# STM32.net
KiCad netlist of a schematic drawn in Altium Designer
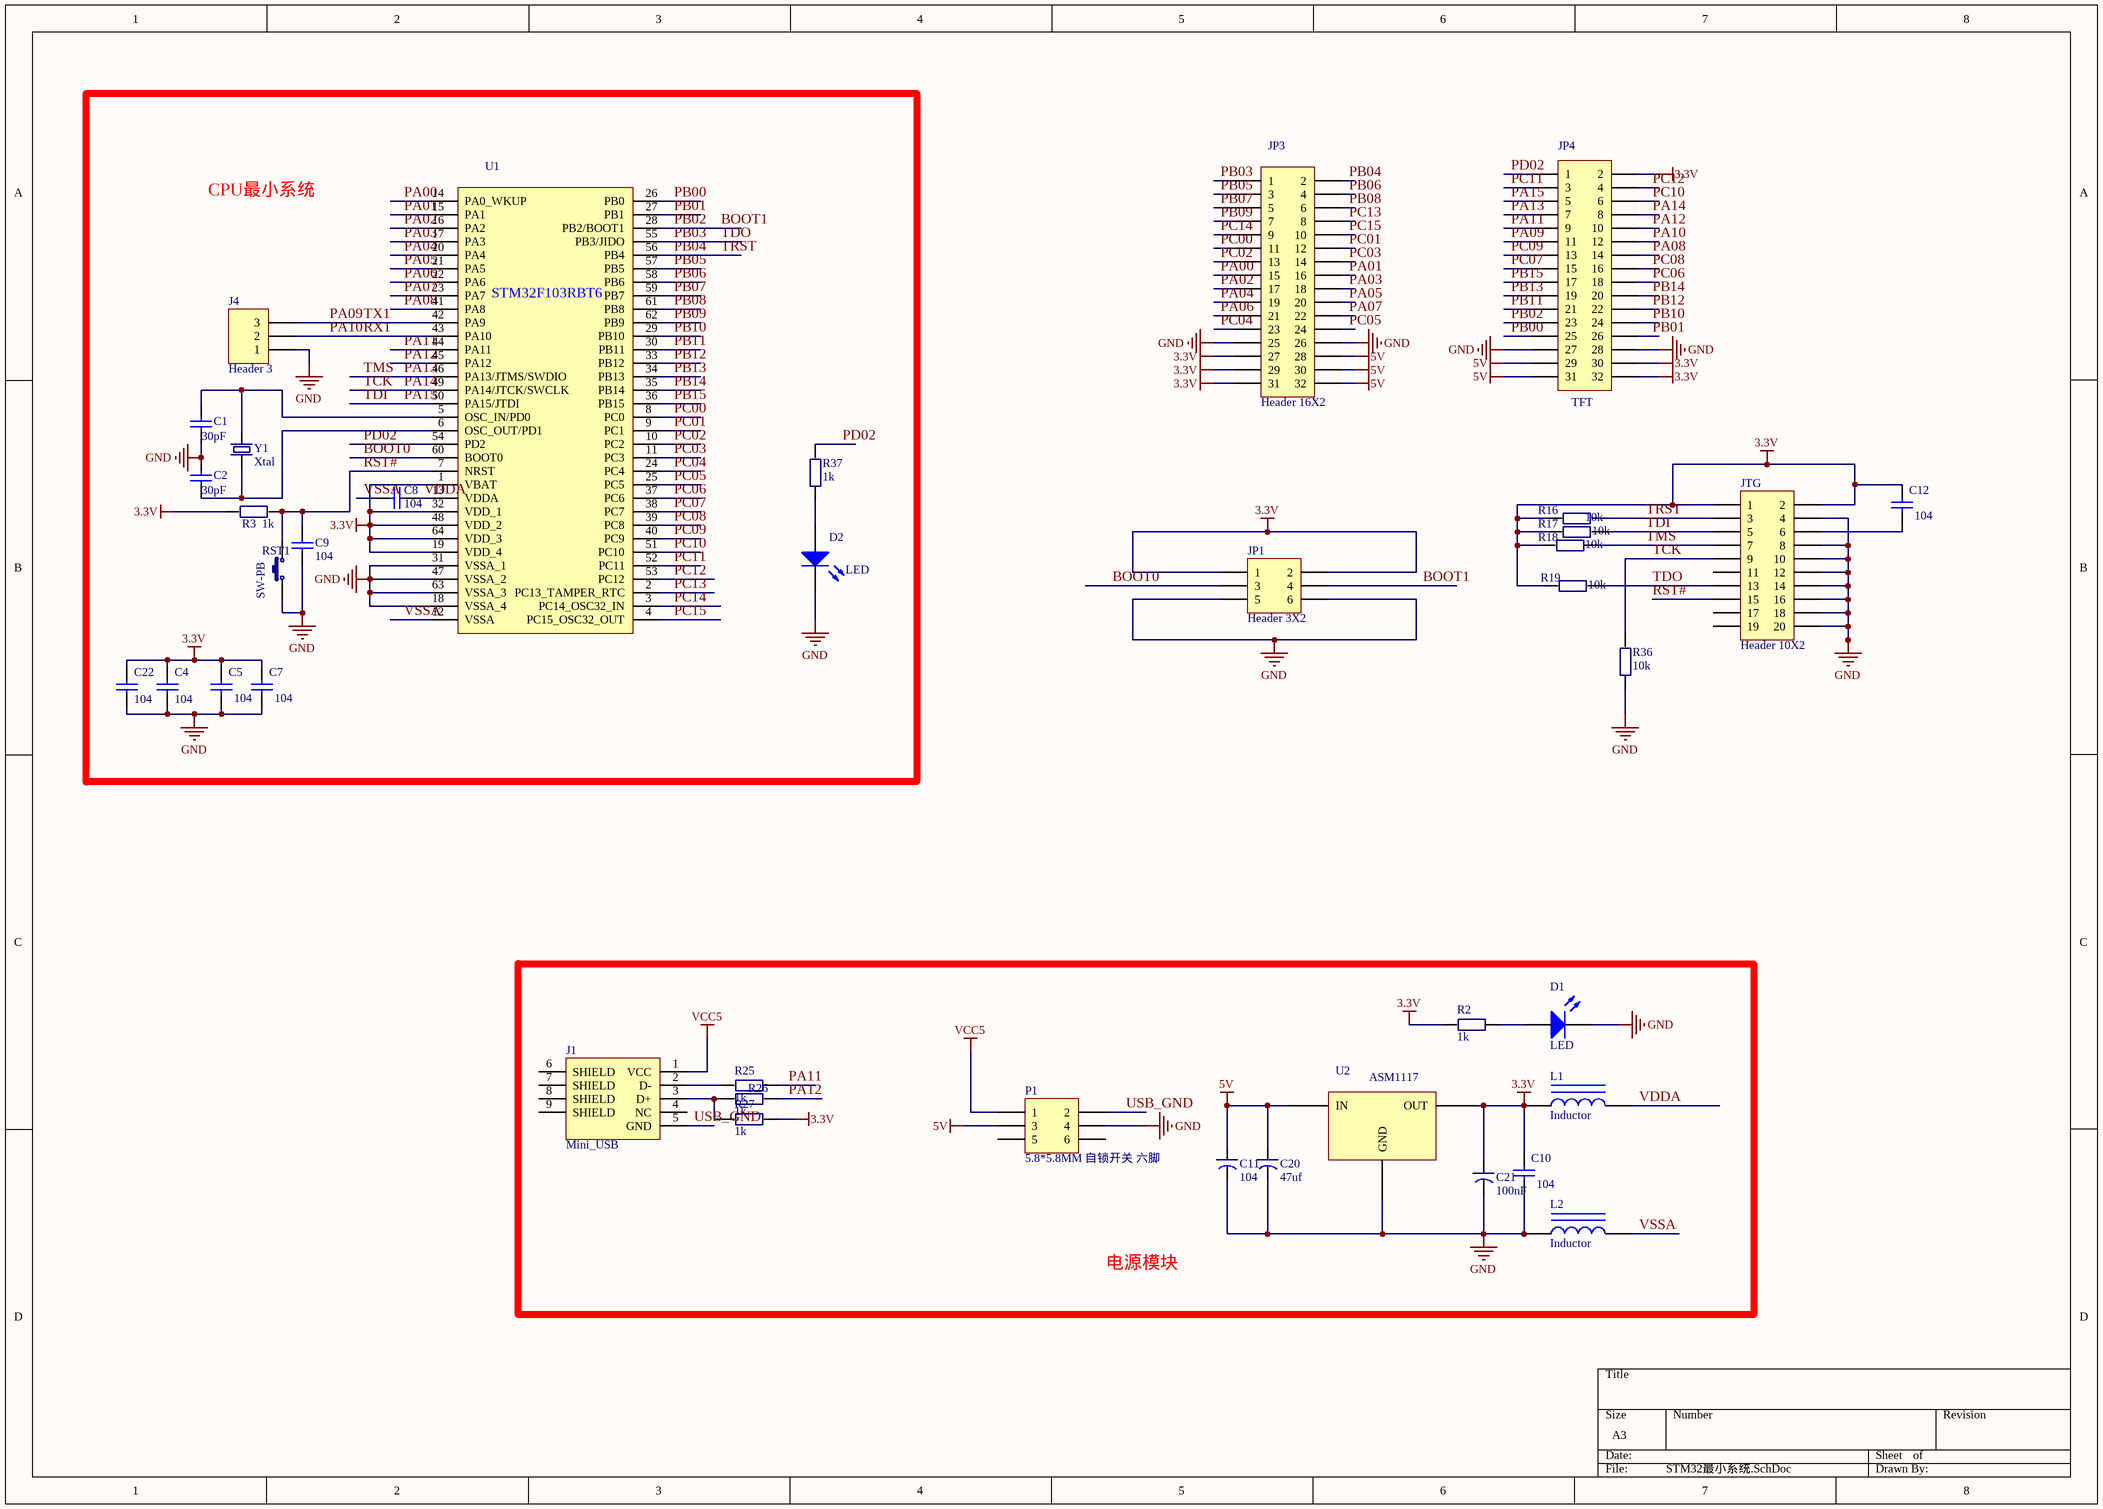
[diagram p0: STM32最小系统.SchDoc]

(export (version "E")
  (design (tool "Eeschema 10.0.6"))
  (components
    (comp (ref "C1")
      (value "30pF")
      (footprint "C0805")
      (description "Capacitor")
      (fields (field (name "Comment") "Cap") (field (name "PUBLISHER") "Altium Limited"))
      (libsource (lib "M051电子称") (part "Cap"))
    )
    (comp (ref "C2")
      (value "30pF")
      (footprint "C0805")
      (description "Capacitor")
      (fields (field (name "Comment") "Cap") (field (name "PUBLISHER") "Altium Limited"))
      (libsource (lib "M051电子称") (part "Cap"))
    )
    (comp (ref "C4")
      (value "104")
      (footprint "C0805")
      (description "Capacitor")
      (fields (field (name "Comment") "Cap") (field (name "PUBLISHER") "Altium Limited"))
      (libsource (lib "M051电子称") (part "Cap"))
    )
    (comp (ref "C5")
      (value "104")
      (footprint "C0805")
      (description "Capacitor")
      (fields (field (name "Comment") "Cap") (field (name "PUBLISHER") "Altium Limited"))
      (libsource (lib "M051电子称") (part "Cap"))
    )
    (comp (ref "C7")
      (value "104")
      (footprint "C0805")
      (description "Capacitor")
      (fields (field (name "Comment") "Cap") (field (name "PUBLISHER") "Altium Limited"))
      (libsource (lib "M051电子称") (part "Cap"))
    )
    (comp (ref "C8")
      (value "104")
      (footprint "C0805")
      (description "Capacitor")
      (fields (field (name "Comment") "Cap") (field (name "PUBLISHER") "Altium Limited"))
      (libsource (lib "M051电子称") (part "Cap"))
    )
    (comp (ref "C9")
      (value "104")
      (footprint "C0805")
      (description "Capacitor")
      (fields (field (name "Comment") "Cap") (field (name "PUBLISHER") "Altium Limited"))
      (libsource (lib "M051电子称") (part "Cap"))
    )
    (comp (ref "C10")
      (value "104")
      (footprint "C0805")
      (description "Capacitor")
      (fields (field (name "Comment") "Cap") (field (name "PUBLISHER") "Altium Limited"))
      (libsource (lib "M051电子称") (part "Cap"))
    )
    (comp (ref "C11")
      (value "104")
      (footprint "C0805")
      (fields (field (name "Comment") "Capacitor"))
      (libsource (lib "My Devices") (part "Capacitor"))
    )
    (comp (ref "C12")
      (value "104")
      (footprint "C0805")
      (description "Capacitor")
      (fields (field (name "Comment") "Cap") (field (name "PUBLISHER") "Altium Limited"))
      (libsource (lib "M051电子称") (part "Cap"))
    )
    (comp (ref "C20")
      (value "47uf")
      (footprint "47uF_25V")
      (fields (field (name "Comment") "Capacitor"))
      (libsource (lib "My Devices") (part "Capacitor"))
    )
    (comp (ref "C21")
      (value "100nF")
      (footprint "47uF_25V")
      (fields (field (name "Comment") "Capacitor"))
      (libsource (lib "My Devices") (part "Capacitor"))
    )
    (comp (ref "C22")
      (value "104")
      (footprint "C0805")
      (description "Capacitor")
      (fields (field (name "Comment") "Cap") (field (name "PUBLISHER") "Altium Limited"))
      (libsource (lib "M051电子称") (part "Cap"))
    )
    (comp (ref "D1") (value "LED") (footprint "0805D") (libsource (lib "My Devices") (part "LED")))
    (comp (ref "D2") (value "LED") (footprint "0805D") (libsource (lib "My Devices") (part "LED")))
    (comp (ref "J1")
      (value "Mini_USB")
      (footprint "Mini_USB")
      (libsource (lib "My Devices") (part "Mini_USB"))
    )
    (comp (ref "J4")
      (value "Header 3")
      (footprint "HDR1X3")
      (description "Header, 3-Pin")
      (fields (field (name "PUBLISHER") "Altium Limited"))
      (libsource (lib "Header Devices") (part "Header 3"))
    )
    (comp (ref "JP1")
      (value "Header 3X2")
      (footprint "HDR2X3")
      (description "Header, 3-Pin, Dual row")
      (fields (field (name "PUBLISHER") "Altium Limited"))
      (libsource (lib "Header Devices") (part "Header 3X2"))
    )
    (comp (ref "JP3")
      (value "Header 16X2")
      (footprint "HDR2X16")
      (description "Header, 16-Pin, Dual row")
      (fields (field (name "PUBLISHER") "Altium Limited"))
      (libsource (lib "Header Devices") (part "Header 16X2"))
    )
    (comp (ref "JP4")
      (value "TFT")
      (footprint "HDR2X16")
      (description "Header, 16-Pin, Dual row")
      (fields (field (name "PUBLISHER") "Altium Limited"))
      (libsource (lib "Header Devices") (part "Header 16X2"))
    )
    (comp (ref "JTG")
      (value "Header 10X2")
      (footprint "HDR2X10")
      (description "Header, 10-Pin, Dual row")
      (fields (field (name "PUBLISHER") "Altium Limited"))
      (libsource (lib "Header Devices") (part "Header 10X2"))
    )
    (comp (ref "L1") (value "Inductor") (footprint "C0805") (libsource (lib "My Devices") (part "Inductor")))
    (comp (ref "L2") (value "Inductor") (footprint "C0805") (libsource (lib "My Devices") (part "Inductor")))
    (comp (ref "P1")
      (value "5.8*5.8MM 自锁开关 六脚")
      (footprint "5.8*5.8MM 自锁开关 六脚")
      (libsource (lib "自制库-程文") (part "5.8*5.8MM 自锁开关 六脚"))
    )
    (comp (ref "R2")
      (value "1k")
      (footprint "R0805")
      (fields (field (name "Comment") "Resistor"))
      (libsource (lib "My Devices") (part "Resistor"))
    )
    (comp (ref "R3")
      (value "1k")
      (footprint "R0805")
      (fields (field (name "Comment") "Resistor"))
      (libsource (lib "My Devices") (part "Resistor"))
    )
    (comp (ref "R16")
      (value "10k")
      (footprint "R0805")
      (fields (field (name "Comment") "Resistor"))
      (libsource (lib "My Devices") (part "Resistor"))
    )
    (comp (ref "R17")
      (value "10k")
      (footprint "R0805")
      (fields (field (name "Comment") "Resistor"))
      (libsource (lib "My Devices") (part "Resistor"))
    )
    (comp (ref "R18")
      (value "10k")
      (footprint "R0805")
      (fields (field (name "Comment") "Resistor"))
      (libsource (lib "My Devices") (part "Resistor"))
    )
    (comp (ref "R19")
      (value "10k")
      (footprint "R0805")
      (fields (field (name "Comment") "Resistor"))
      (libsource (lib "My Devices") (part "Resistor"))
    )
    (comp (ref "R25")
      (value "1k")
      (footprint "R0805")
      (fields (field (name "Comment") "Resistor"))
      (libsource (lib "My Devices") (part "Resistor"))
    )
    (comp (ref "R26")
      (value "1k")
      (footprint "R0805")
      (fields (field (name "Comment") "Resistor"))
      (libsource (lib "My Devices") (part "Resistor"))
    )
    (comp (ref "R27")
      (value "1k")
      (footprint "R0805")
      (fields (field (name "Comment") "Resistor"))
      (libsource (lib "My Devices") (part "Resistor"))
    )
    (comp (ref "R36")
      (value "10k")
      (footprint "R0805")
      (fields (field (name "Comment") "Resistor"))
      (libsource (lib "My Devices") (part "Resistor"))
    )
    (comp (ref "R37")
      (value "1k")
      (footprint "R0805")
      (fields (field (name "Comment") "Resistor"))
      (libsource (lib "My Devices") (part "Resistor"))
    )
    (comp (ref "RST1") (value "SW-PB") (footprint "TD-19XA") (libsource (lib "My Devices") (part "Switch")))
    (comp (ref "U1")
      (value "STM32F103RBT6")
      (footprint "LQFP-64N")
      (libsource (lib "My Devices") (part "STM32F103RBT6"))
    )
    (comp (ref "U2") (value "ASM1117") (footprint "SOT-223") (libsource (lib "电源类集成库") (part "ASM1117")))
    (comp (ref "Y1") (value "Xtal") (footprint "CRYSTAL") (libsource (lib "My Devices") (part "Xtal")))
  )
  (nets
    (net (code "1") (name "/BOOT0") (class "Default")
      (node (ref "JP1") (pin "3") (pinfunction "3_3") (pintype "passive"))
      (node (ref "U1") (pin "60") (pinfunction "BOOT0_60") (pintype "passive"))
    )
    (net (code "2") (name "/BOOT1") (class "Default")
      (node (ref "JP1") (pin "4") (pinfunction "4_4") (pintype "passive"))
      (node (ref "JP4") (pin "23") (pinfunction "23_23") (pintype "passive"))
      (node (ref "U1") (pin "28") (pinfunction "PB2/BOOT1_28") (pintype "passive"))
    )
    (net (code "3") (name "/PA00") (class "Default")
      (node (ref "JP3") (pin "15") (pinfunction "15_15") (pintype "passive"))
      (node (ref "U1") (pin "14") (pinfunction "PA0_WKUP_14") (pintype "passive"))
    )
    (net (code "4") (name "/PA01") (class "Default")
      (node (ref "JP3") (pin "16") (pinfunction "16_16") (pintype "passive"))
      (node (ref "U1") (pin "15") (pinfunction "PA1_15") (pintype "passive"))
    )
    (net (code "5") (name "/PA02") (class "Default")
      (node (ref "JP3") (pin "17") (pinfunction "17_17") (pintype "passive"))
      (node (ref "U1") (pin "16") (pinfunction "PA2_16") (pintype "passive"))
    )
    (net (code "6") (name "/PA03") (class "Default")
      (node (ref "JP3") (pin "18") (pinfunction "18_18") (pintype "passive"))
      (node (ref "U1") (pin "17") (pinfunction "PA3_17") (pintype "passive"))
    )
    (net (code "7") (name "/PA04") (class "Default")
      (node (ref "JP3") (pin "19") (pinfunction "19_19") (pintype "passive"))
      (node (ref "U1") (pin "20") (pinfunction "PA4_20") (pintype "passive"))
    )
    (net (code "8") (name "/PA05") (class "Default")
      (node (ref "JP3") (pin "20") (pinfunction "20_20") (pintype "passive"))
      (node (ref "U1") (pin "21") (pinfunction "PA5_21") (pintype "passive"))
    )
    (net (code "9") (name "/PA06") (class "Default")
      (node (ref "JP3") (pin "21") (pinfunction "21_21") (pintype "passive"))
      (node (ref "U1") (pin "22") (pinfunction "PA6_22") (pintype "passive"))
    )
    (net (code "10") (name "/PA07") (class "Default")
      (node (ref "JP3") (pin "22") (pinfunction "22_22") (pintype "passive"))
      (node (ref "U1") (pin "23") (pinfunction "PA7_23") (pintype "passive"))
    )
    (net (code "11") (name "/PA08") (class "Default")
      (node (ref "JP4") (pin "14") (pinfunction "14_14") (pintype "passive"))
      (node (ref "U1") (pin "41") (pinfunction "PA8_41") (pintype "passive"))
    )
    (net (code "12") (name "/PA09") (class "Default")
      (node (ref "J4") (pin "3") (pinfunction "3_3") (pintype "passive"))
      (node (ref "JP4") (pin "11") (pinfunction "11_11") (pintype "passive"))
      (node (ref "U1") (pin "42") (pinfunction "PA9_42") (pintype "passive"))
    )
    (net (code "13") (name "/PA10") (class "Default")
      (node (ref "J4") (pin "2") (pinfunction "2_2") (pintype "passive"))
      (node (ref "JP4") (pin "12") (pinfunction "12_12") (pintype "passive"))
      (node (ref "U1") (pin "43") (pinfunction "PA10_43") (pintype "passive"))
    )
    (net (code "14") (name "/PA11") (class "Default")
      (node (ref "JP4") (pin "9") (pinfunction "9_9") (pintype "passive"))
      (node (ref "R25") (pin "1") (pintype "passive"))
      (node (ref "U1") (pin "44") (pinfunction "PA11_44") (pintype "passive"))
    )
    (net (code "15") (name "/PA12") (class "Default")
      (node (ref "JP4") (pin "10") (pinfunction "10_10") (pintype "passive"))
      (node (ref "R26") (pin "1") (pintype "passive"))
      (node (ref "U1") (pin "45") (pinfunction "PA12_45") (pintype "passive"))
    )
    (net (code "16") (name "/PA13") (class "Default")
      (node (ref "JP4") (pin "7") (pinfunction "7_7") (pintype "passive"))
      (node (ref "JTG") (pin "7") (pinfunction "7_7") (pintype "passive"))
      (node (ref "R18") (pin "1") (pintype "passive"))
      (node (ref "U1") (pin "46") (pinfunction "PA13/JTMS/SWDIO_46") (pintype "passive"))
    )
    (net (code "17") (name "/PA14") (class "Default")
      (node (ref "JP4") (pin "8") (pinfunction "8_8") (pintype "passive"))
      (node (ref "JTG") (pin "9") (pinfunction "9_9") (pintype "passive"))
      (node (ref "R36") (pin "1") (pintype "passive"))
      (node (ref "U1") (pin "49") (pinfunction "PA14/JTCK/SWCLK_49") (pintype "passive"))
    )
    (net (code "18") (name "/PA15") (class "Default")
      (node (ref "JP4") (pin "5") (pinfunction "5_5") (pintype "passive"))
      (node (ref "JTG") (pin "5") (pinfunction "5_5") (pintype "passive"))
      (node (ref "R17") (pin "1") (pintype "passive"))
      (node (ref "U1") (pin "50") (pinfunction "PA15/JTDI_50") (pintype "passive"))
    )
    (net (code "19") (name "/PB00") (class "Default")
      (node (ref "JP4") (pin "25") (pinfunction "25_25") (pintype "passive"))
      (node (ref "U1") (pin "26") (pinfunction "PB0_26") (pintype "passive"))
    )
    (net (code "20") (name "/PB01") (class "Default")
      (node (ref "JP4") (pin "26") (pinfunction "26_26") (pintype "passive"))
      (node (ref "U1") (pin "27") (pinfunction "PB1_27") (pintype "passive"))
    )
    (net (code "21") (name "/PB03") (class "Default")
      (node (ref "JP3") (pin "1") (pinfunction "1_1") (pintype "passive"))
      (node (ref "JTG") (pin "13") (pinfunction "13_13") (pintype "passive"))
      (node (ref "R19") (pin "1") (pintype "passive"))
      (node (ref "U1") (pin "55") (pinfunction "PB3/JIDO_55") (pintype "passive"))
    )
    (net (code "22") (name "/PB04") (class "Default")
      (node (ref "JP3") (pin "2") (pinfunction "2_2") (pintype "passive"))
      (node (ref "JTG") (pin "3") (pinfunction "3_3") (pintype "passive"))
      (node (ref "R16") (pin "1") (pintype "passive"))
      (node (ref "U1") (pin "56") (pinfunction "PB4_56") (pintype "passive"))
    )
    (net (code "23") (name "/PB05") (class "Default")
      (node (ref "JP3") (pin "3") (pinfunction "3_3") (pintype "passive"))
      (node (ref "U1") (pin "57") (pinfunction "PB5_57") (pintype "passive"))
    )
    (net (code "24") (name "/PB06") (class "Default")
      (node (ref "JP3") (pin "4") (pinfunction "4_4") (pintype "passive"))
      (node (ref "U1") (pin "58") (pinfunction "PB6_58") (pintype "passive"))
    )
    (net (code "25") (name "/PB07") (class "Default")
      (node (ref "JP3") (pin "5") (pinfunction "5_5") (pintype "passive"))
      (node (ref "U1") (pin "59") (pinfunction "PB7_59") (pintype "passive"))
    )
    (net (code "26") (name "/PB08") (class "Default")
      (node (ref "JP3") (pin "6") (pinfunction "6_6") (pintype "passive"))
      (node (ref "U1") (pin "61") (pinfunction "PB8_61") (pintype "passive"))
    )
    (net (code "27") (name "/PB09") (class "Default")
      (node (ref "JP3") (pin "7") (pinfunction "7_7") (pintype "passive"))
      (node (ref "U1") (pin "62") (pinfunction "PB9_62") (pintype "passive"))
    )
    (net (code "28") (name "/PB10") (class "Default")
      (node (ref "JP4") (pin "24") (pinfunction "24_24") (pintype "passive"))
      (node (ref "U1") (pin "29") (pinfunction "PB10_29") (pintype "passive"))
    )
    (net (code "29") (name "/PB11") (class "Default")
      (node (ref "JP4") (pin "21") (pinfunction "21_21") (pintype "passive"))
      (node (ref "U1") (pin "30") (pinfunction "PB11_30") (pintype "passive"))
    )
    (net (code "30") (name "/PB12") (class "Default")
      (node (ref "JP4") (pin "22") (pinfunction "22_22") (pintype "passive"))
      (node (ref "U1") (pin "33") (pinfunction "PB12_33") (pintype "passive"))
    )
    (net (code "31") (name "/PB13") (class "Default")
      (node (ref "JP4") (pin "19") (pinfunction "19_19") (pintype "passive"))
      (node (ref "U1") (pin "34") (pinfunction "PB13_34") (pintype "passive"))
    )
    (net (code "32") (name "/PB14") (class "Default")
      (node (ref "JP4") (pin "20") (pinfunction "20_20") (pintype "passive"))
      (node (ref "U1") (pin "35") (pinfunction "PB14_35") (pintype "passive"))
    )
    (net (code "33") (name "/PB15") (class "Default")
      (node (ref "JP4") (pin "17") (pinfunction "17_17") (pintype "passive"))
      (node (ref "U1") (pin "36") (pinfunction "PB15_36") (pintype "passive"))
    )
    (net (code "34") (name "/PC00") (class "Default")
      (node (ref "JP3") (pin "11") (pinfunction "11_11") (pintype "passive"))
      (node (ref "U1") (pin "8") (pinfunction "PC0_8") (pintype "passive"))
    )
    (net (code "35") (name "/PC01") (class "Default")
      (node (ref "JP3") (pin "12") (pinfunction "12_12") (pintype "passive"))
      (node (ref "U1") (pin "9") (pinfunction "PC1_9") (pintype "passive"))
    )
    (net (code "36") (name "/PC02") (class "Default")
      (node (ref "JP3") (pin "13") (pinfunction "13_13") (pintype "passive"))
      (node (ref "U1") (pin "10") (pinfunction "PC2_10") (pintype "passive"))
    )
    (net (code "37") (name "/PC03") (class "Default")
      (node (ref "JP3") (pin "14") (pinfunction "14_14") (pintype "passive"))
      (node (ref "U1") (pin "11") (pinfunction "PC3_11") (pintype "passive"))
    )
    (net (code "38") (name "/PC04") (class "Default")
      (node (ref "JP3") (pin "23") (pinfunction "23_23") (pintype "passive"))
      (node (ref "U1") (pin "24") (pinfunction "PC4_24") (pintype "passive"))
    )
    (net (code "39") (name "/PC05") (class "Default")
      (node (ref "JP3") (pin "24") (pinfunction "24_24") (pintype "passive"))
      (node (ref "U1") (pin "25") (pinfunction "PC5_25") (pintype "passive"))
    )
    (net (code "40") (name "/PC06") (class "Default")
      (node (ref "JP4") (pin "18") (pinfunction "18_18") (pintype "passive"))
      (node (ref "U1") (pin "37") (pinfunction "PC6_37") (pintype "passive"))
    )
    (net (code "41") (name "/PC07") (class "Default")
      (node (ref "JP4") (pin "15") (pinfunction "15_15") (pintype "passive"))
      (node (ref "U1") (pin "38") (pinfunction "PC7_38") (pintype "passive"))
    )
    (net (code "42") (name "/PC08") (class "Default")
      (node (ref "JP4") (pin "16") (pinfunction "16_16") (pintype "passive"))
      (node (ref "U1") (pin "39") (pinfunction "PC8_39") (pintype "passive"))
    )
    (net (code "43") (name "/PC09") (class "Default")
      (node (ref "JP4") (pin "13") (pinfunction "13_13") (pintype "passive"))
      (node (ref "U1") (pin "40") (pinfunction "PC9_40") (pintype "passive"))
    )
    (net (code "44") (name "/PC10") (class "Default")
      (node (ref "JP4") (pin "6") (pinfunction "6_6") (pintype "passive"))
      (node (ref "U1") (pin "51") (pinfunction "PC10_51") (pintype "passive"))
    )
    (net (code "45") (name "/PC11") (class "Default")
      (node (ref "JP4") (pin "3") (pinfunction "3_3") (pintype "passive"))
      (node (ref "U1") (pin "52") (pinfunction "PC11_52") (pintype "passive"))
    )
    (net (code "46") (name "/PC12") (class "Default")
      (node (ref "JP4") (pin "4") (pinfunction "4_4") (pintype "passive"))
      (node (ref "U1") (pin "53") (pinfunction "PC12_53") (pintype "passive"))
    )
    (net (code "47") (name "/PC13") (class "Default")
      (node (ref "JP3") (pin "8") (pinfunction "8_8") (pintype "passive"))
      (node (ref "U1") (pin "2") (pinfunction "PC13_TAMPER_RTC_2") (pintype "passive"))
    )
    (net (code "48") (name "/PC14") (class "Default")
      (node (ref "JP3") (pin "9") (pinfunction "9_9") (pintype "passive"))
      (node (ref "U1") (pin "3") (pinfunction "PC14_OSC32_IN_3") (pintype "passive"))
    )
    (net (code "49") (name "/PC15") (class "Default")
      (node (ref "JP3") (pin "10") (pinfunction "10_10") (pintype "passive"))
      (node (ref "U1") (pin "4") (pinfunction "PC15_OSC32_OUT_4") (pintype "passive"))
    )
    (net (code "50") (name "/PD02") (class "Default")
      (node (ref "JP4") (pin "1") (pinfunction "1_1") (pintype "passive"))
      (node (ref "R37") (pin "2") (pintype "passive"))
      (node (ref "U1") (pin "54") (pinfunction "PD2_54") (pintype "passive"))
    )
    (net (code "51") (name "/RST#") (class "Default")
      (node (ref "C9") (pin "1") (pinfunction "1_1") (pintype "passive"))
      (node (ref "JTG") (pin "15") (pinfunction "15_15") (pintype "passive"))
      (node (ref "R3") (pin "2") (pintype "passive"))
      (node (ref "RST1") (pin "2") (pinfunction "1_2") (pintype "passive"))
      (node (ref "U1") (pin "7") (pinfunction "NRST_7") (pintype "passive"))
    )
    (net (code "52") (name "/USB_GND") (class "Default")
      (node (ref "J1") (pin "5") (pinfunction "GND_5") (pintype "passive"))
      (node (ref "P1") (pin "2") (pinfunction "2_2") (pintype "passive"))
    )
    (net (code "53") (name "/VDDA") (class "Default")
      (node (ref "C8") (pin "1") (pinfunction "1_1") (pintype "passive"))
      (node (ref "L1") (pin "2") (pinfunction "2_2") (pintype "passive"))
      (node (ref "U1") (pin "13") (pinfunction "VDDA_13") (pintype "passive"))
    )
    (net (code "54") (name "/VSSA") (class "Default")
      (node (ref "C8") (pin "2") (pinfunction "2_2") (pintype "passive"))
      (node (ref "L2") (pin "2") (pinfunction "2_2") (pintype "passive"))
      (node (ref "U1") (pin "12") (pinfunction "VSSA_12") (pintype "passive"))
    )
    (net (code "55") (name "3.3V") (class "Default")
      (node (ref "C10") (pin "1") (pinfunction "1_1") (pintype "passive"))
      (node (ref "C12") (pin "1") (pinfunction "1_1") (pintype "passive"))
      (node (ref "C21") (pin "1") (pinfunction "0_1") (pintype "passive"))
      (node (ref "C22") (pin "1") (pinfunction "1_1") (pintype "passive"))
      (node (ref "C4") (pin "1") (pinfunction "1_1") (pintype "passive"))
      (node (ref "C5") (pin "1") (pinfunction "1_1") (pintype "passive"))
      (node (ref "C7") (pin "1") (pinfunction "1_1") (pintype "passive"))
      (node (ref "JP1") (pin "1") (pinfunction "1_1") (pintype "passive"))
      (node (ref "JP1") (pin "2") (pinfunction "2_2") (pintype "passive"))
      (node (ref "JP3") (pin "27") (pinfunction "27_27") (pintype "passive"))
      (node (ref "JP3") (pin "29") (pinfunction "29_29") (pintype "passive"))
      (node (ref "JP3") (pin "31") (pinfunction "31_31") (pintype "passive"))
      (node (ref "JP4") (pin "2") (pinfunction "2_2") (pintype "passive"))
      (node (ref "JP4") (pin "30") (pinfunction "30_30") (pintype "passive"))
      (node (ref "JP4") (pin "32") (pinfunction "32_32") (pintype "passive"))
      (node (ref "JTG") (pin "1") (pinfunction "1_1") (pintype "passive"))
      (node (ref "JTG") (pin "2") (pinfunction "2_2") (pintype "passive"))
      (node (ref "L1") (pin "1") (pinfunction "1_1") (pintype "passive"))
      (node (ref "R16") (pin "2") (pintype "passive"))
      (node (ref "R17") (pin "2") (pintype "passive"))
      (node (ref "R18") (pin "2") (pintype "passive"))
      (node (ref "R19") (pin "2") (pintype "passive"))
      (node (ref "R2") (pin "2") (pintype "passive"))
      (node (ref "R27") (pin "1") (pintype "passive"))
      (node (ref "R3") (pin "1") (pintype "passive"))
      (node (ref "U1") (pin "1") (pinfunction "VBAT_1") (pintype "passive"))
      (node (ref "U1") (pin "19") (pinfunction "VDD_4_19") (pintype "passive"))
      (node (ref "U1") (pin "32") (pinfunction "VDD_1_32") (pintype "passive"))
      (node (ref "U1") (pin "48") (pinfunction "VDD_2_48") (pintype "passive"))
      (node (ref "U1") (pin "64") (pinfunction "VDD_3_64") (pintype "passive"))
      (node (ref "U2") (pin "2") (pinfunction "OUT_2") (pintype "passive"))
    )
    (net (code "56") (name "5V") (class "Default")
      (node (ref "C11") (pin "1") (pinfunction "0_1") (pintype "passive"))
      (node (ref "C20") (pin "1") (pinfunction "0_1") (pintype "passive"))
      (node (ref "JP3") (pin "28") (pinfunction "28_28") (pintype "passive"))
      (node (ref "JP3") (pin "30") (pinfunction "30_30") (pintype "passive"))
      (node (ref "JP3") (pin "32") (pinfunction "32_32") (pintype "passive"))
      (node (ref "JP4") (pin "29") (pinfunction "29_29") (pintype "passive"))
      (node (ref "JP4") (pin "31") (pinfunction "31_31") (pintype "passive"))
      (node (ref "P1") (pin "3") (pinfunction "3_3") (pintype "passive"))
      (node (ref "U2") (pin "3") (pinfunction "IN_3") (pintype "passive"))
    )
    (net (code "57") (name "GND") (class "Default")
      (node (ref "C1") (pin "1") (pinfunction "1_1") (pintype "passive"))
      (node (ref "C10") (pin "2") (pinfunction "2_2") (pintype "passive"))
      (node (ref "C11") (pin "2") (pinfunction "1_2") (pintype "passive"))
      (node (ref "C2") (pin "2") (pinfunction "2_2") (pintype "passive"))
      (node (ref "C20") (pin "2") (pinfunction "1_2") (pintype "passive"))
      (node (ref "C21") (pin "2") (pinfunction "1_2") (pintype "passive"))
      (node (ref "C22") (pin "2") (pinfunction "2_2") (pintype "passive"))
      (node (ref "C4") (pin "2") (pinfunction "2_2") (pintype "passive"))
      (node (ref "C5") (pin "2") (pinfunction "2_2") (pintype "passive"))
      (node (ref "C7") (pin "2") (pinfunction "2_2") (pintype "passive"))
      (node (ref "C9") (pin "2") (pinfunction "2_2") (pintype "passive"))
      (node (ref "D1") (pin "2") (pinfunction "K_2") (pintype "passive"))
      (node (ref "D2") (pin "2") (pinfunction "K_2") (pintype "passive"))
      (node (ref "J4") (pin "1") (pinfunction "1_1") (pintype "passive"))
      (node (ref "JP1") (pin "5") (pinfunction "5_5") (pintype "passive"))
      (node (ref "JP1") (pin "6") (pinfunction "6_6") (pintype "passive"))
      (node (ref "JP3") (pin "25") (pinfunction "25_25") (pintype "passive"))
      (node (ref "JP3") (pin "26") (pinfunction "26_26") (pintype "passive"))
      (node (ref "JP4") (pin "27") (pinfunction "27_27") (pintype "passive"))
      (node (ref "JP4") (pin "28") (pinfunction "28_28") (pintype "passive"))
      (node (ref "JTG") (pin "10") (pinfunction "10_10") (pintype "passive"))
      (node (ref "JTG") (pin "12") (pinfunction "12_12") (pintype "passive"))
      (node (ref "JTG") (pin "14") (pinfunction "14_14") (pintype "passive"))
      (node (ref "JTG") (pin "16") (pinfunction "16_16") (pintype "passive"))
      (node (ref "JTG") (pin "18") (pinfunction "18_18") (pintype "passive"))
      (node (ref "JTG") (pin "20") (pinfunction "20_20") (pintype "passive"))
      (node (ref "JTG") (pin "4") (pinfunction "4_4") (pintype "passive"))
      (node (ref "JTG") (pin "8") (pinfunction "8_8") (pintype "passive"))
      (node (ref "L2") (pin "1") (pinfunction "1_1") (pintype "passive"))
      (node (ref "P1") (pin "4") (pinfunction "4_4") (pintype "passive"))
      (node (ref "R36") (pin "2") (pintype "passive"))
      (node (ref "RST1") (pin "1") (pinfunction "0_1") (pintype "passive"))
      (node (ref "U1") (pin "18") (pinfunction "VSSA_4_18") (pintype "passive"))
      (node (ref "U1") (pin "31") (pinfunction "VSSA_1_31") (pintype "passive"))
      (node (ref "U1") (pin "47") (pinfunction "VSSA_2_47") (pintype "passive"))
      (node (ref "U1") (pin "63") (pinfunction "VSSA_3_63") (pintype "passive"))
      (node (ref "U2") (pin "1") (pinfunction "GND_1") (pintype "passive"))
    )
    (net (code "58") (name "Net-(C12-Pad2)") (class "Default")
      (node (ref "C12") (pin "2") (pinfunction "2_2") (pintype "passive"))
      (node (ref "JTG") (pin "6") (pinfunction "6_6") (pintype "passive"))
    )
    (net (code "59") (name "Net-(D1-A)") (class "Default")
      (node (ref "D1") (pin "1") (pinfunction "A_1") (pintype "passive"))
      (node (ref "R2") (pin "1") (pintype "passive"))
    )
    (net (code "60") (name "Net-(D2-A)") (class "Default")
      (node (ref "D2") (pin "1") (pinfunction "A_1") (pintype "passive"))
      (node (ref "R37") (pin "1") (pintype "passive"))
    )
    (net (code "61") (name "Net-(J1-D+)") (class "Default")
      (node (ref "J1") (pin "3") (pinfunction "D+_3") (pintype "passive"))
      (node (ref "R26") (pin "2") (pintype "passive"))
      (node (ref "R27") (pin "2") (pintype "passive"))
    )
    (net (code "62") (name "Net-(J1-D-)") (class "Default")
      (node (ref "J1") (pin "2") (pinfunction "D-_2") (pintype "passive"))
      (node (ref "R25") (pin "2") (pintype "passive"))
    )
    (net (code "63") (name "Net-(U1-OSC_IN{slash}PD0)") (class "Default")
      (node (ref "C1") (pin "2") (pinfunction "2_2") (pintype "passive"))
      (node (ref "U1") (pin "5") (pinfunction "OSC_IN/PD0_5") (pintype "passive"))
      (node (ref "Y1") (pin "2") (pinfunction "1_2") (pintype "passive"))
    )
    (net (code "64") (name "Net-(U1-OSC_OUT{slash}PD1)") (class "Default")
      (node (ref "C2") (pin "1") (pinfunction "1_1") (pintype "passive"))
      (node (ref "U1") (pin "6") (pinfunction "OSC_OUT/PD1_6") (pintype "passive"))
      (node (ref "Y1") (pin "1") (pinfunction "0_1") (pintype "passive"))
    )
    (net (code "65") (name "VCC5") (class "Default")
      (node (ref "J1") (pin "1") (pinfunction "VCC_1") (pintype "passive"))
      (node (ref "P1") (pin "1") (pinfunction "1_1") (pintype "passive"))
    )
    (net (code "66") (name "unconnected-(J1-NC-Pad4)") (class "Default")
      (node (ref "J1") (pin "4") (pinfunction "NC_4") (pintype "passive"))
    )
    (net (code "67") (name "unconnected-(J1-SHIELD-Pad6)") (class "Default")
      (node (ref "J1") (pin "6") (pinfunction "SHIELD_6") (pintype "passive"))
    )
    (net (code "68") (name "unconnected-(J1-SHIELD-Pad7)") (class "Default")
      (node (ref "J1") (pin "7") (pinfunction "SHIELD_7") (pintype "passive"))
    )
    (net (code "69") (name "unconnected-(J1-SHIELD-Pad8)") (class "Default")
      (node (ref "J1") (pin "8") (pinfunction "SHIELD_8") (pintype "passive"))
    )
    (net (code "70") (name "unconnected-(J1-SHIELD-Pad9)") (class "Default")
      (node (ref "J1") (pin "9") (pinfunction "SHIELD_9") (pintype "passive"))
    )
    (net (code "71") (name "unconnected-(JTG-Pad11)") (class "Default")
      (node (ref "JTG") (pin "11") (pinfunction "11_11") (pintype "passive"))
    )
    (net (code "72") (name "unconnected-(JTG-Pad17)") (class "Default")
      (node (ref "JTG") (pin "17") (pinfunction "17_17") (pintype "passive"))
    )
    (net (code "73") (name "unconnected-(JTG-Pad19)") (class "Default")
      (node (ref "JTG") (pin "19") (pinfunction "19_19") (pintype "passive"))
    )
    (net (code "74") (name "unconnected-(P1-Pad5)") (class "Default")
      (node (ref "P1") (pin "5") (pinfunction "5_5") (pintype "passive"))
    )
    (net (code "75") (name "unconnected-(P1-Pad6)") (class "Default")
      (node (ref "P1") (pin "6") (pinfunction "6_6") (pintype "passive"))
    )
  )
)
